# Control.net
KiCad netlist of a schematic drawn in Altium Designer
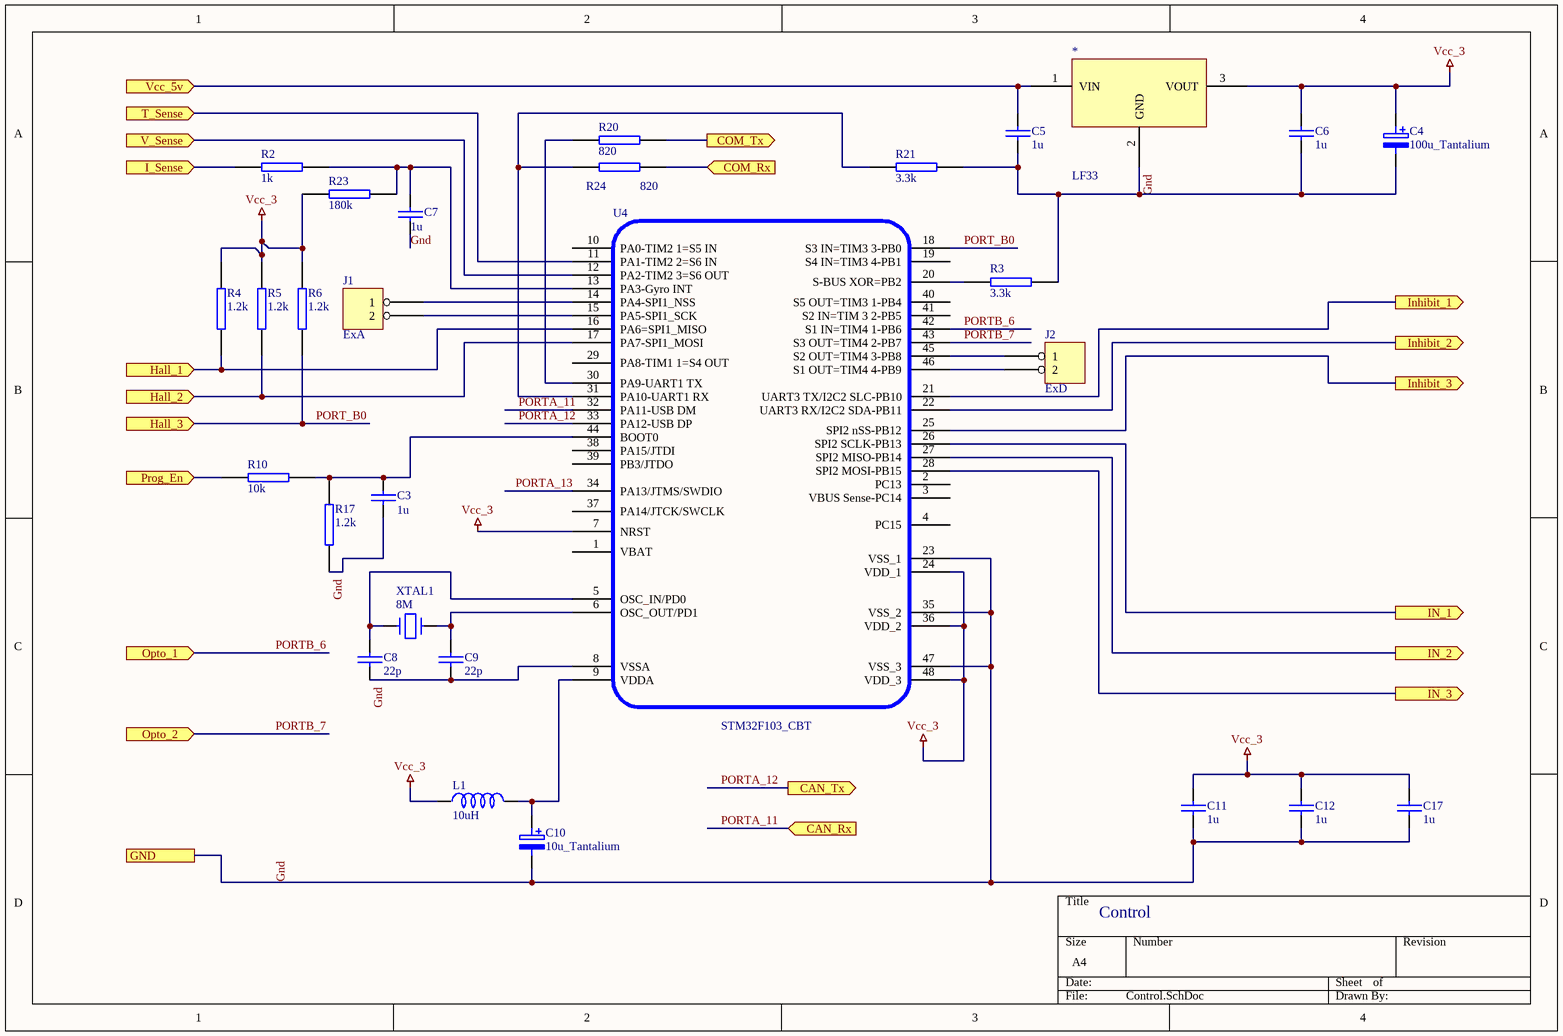
[diagram p0: Control.SchDoc]

(export (version "E")
  (design (tool "Eeschema 10.0.6"))
  (components
    (comp (ref "*") (value "LF33") (footprint "Dpak") (libsource (lib "CustomLib_Ver01") (part "LF33")))
    (comp (ref "C3")
      (value "1u")
      (footprint "1206_SMD")
      (description "Capacitor")
      (libsource (lib "Sch_Lib_24") (part "CAP"))
    )
    (comp (ref "C4")
      (value "100u_Tantalium")
      (footprint "Tantalum_9545")
      (libsource (lib "Sch_Lib_24") (part "CAP_ELECTRO"))
    )
    (comp (ref "C5")
      (value "1u")
      (footprint "1206_SMD")
      (description "Capacitor")
      (libsource (lib "Sch_Lib_24") (part "CAP"))
    )
    (comp (ref "C6")
      (value "1u")
      (footprint "1206_SMD")
      (description "Capacitor")
      (libsource (lib "Sch_Lib_24") (part "CAP"))
    )
    (comp (ref "C7")
      (value "1u")
      (footprint "1206_SMD")
      (description "Capacitor")
      (libsource (lib "Sch_Lib_24") (part "CAP"))
    )
    (comp (ref "C8")
      (value "22p")
      (footprint "0805")
      (description "Capacitor")
      (libsource (lib "Sch_Lib_24") (part "CAP"))
    )
    (comp (ref "C9")
      (value "22p")
      (footprint "0805")
      (description "Capacitor")
      (libsource (lib "Sch_Lib_24") (part "CAP"))
    )
    (comp (ref "C10")
      (value "10u_Tantalium")
      (footprint "Tantalum_9545")
      (libsource (lib "Sch_Lib_24") (part "CAP_ELECTRO"))
    )
    (comp (ref "C11")
      (value "1u")
      (footprint "1206_SMD")
      (description "Capacitor")
      (libsource (lib "Sch_Lib_24") (part "CAP"))
    )
    (comp (ref "C12")
      (value "1u")
      (footprint "1206_SMD")
      (description "Capacitor")
      (libsource (lib "Sch_Lib_24") (part "CAP"))
    )
    (comp (ref "C17")
      (value "1u")
      (footprint "1206_SMD")
      (description "Capacitor")
      (libsource (lib "Sch_Lib_24") (part "CAP"))
    )
    (comp (ref "J1") (value "ExA") (footprint "MHDR1X2") (libsource (lib "Sch_Lib_24") (part "HEADER 2")))
    (comp (ref "J2") (value "ExD") (footprint "MHDR1X2") (libsource (lib "") (part "HEADER 2_1")))
    (comp (ref "L1") (value "10uH") (footprint "1206_SMD") (libsource (lib "Sch_Lib_24") (part "INDUCTOR")))
    (comp (ref "R2") (value "1k") (footprint "0805") (libsource (lib "Sch_Lib_24") (part "RES2")))
    (comp (ref "R3") (value "3.3k") (footprint "0805") (libsource (lib "Sch_Lib_24") (part "RES2")))
    (comp (ref "R4") (value "1.2k") (footprint "1206_SMD") (libsource (lib "Sch_Lib_24") (part "RES2")))
    (comp (ref "R5") (value "1.2k") (footprint "1206_SMD") (libsource (lib "Sch_Lib_24") (part "RES2")))
    (comp (ref "R6") (value "1.2k") (footprint "1206_SMD") (libsource (lib "Sch_Lib_24") (part "RES2")))
    (comp (ref "R10") (value "10k") (footprint "0805") (libsource (lib "Sch_Lib_24") (part "RES2")))
    (comp (ref "R17") (value "1.2k") (footprint "0805") (libsource (lib "Sch_Lib_24") (part "RES2")))
    (comp (ref "R20") (value "820") (footprint "0805") (libsource (lib "Sch_Lib_24") (part "RES2")))
    (comp (ref "R21") (value "3.3k") (footprint "0805") (libsource (lib "Sch_Lib_24") (part "RES2")))
    (comp (ref "R23") (value "180k") (footprint "0805") (libsource (lib "Sch_Lib_24") (part "RES2")))
    (comp (ref "R24") (value "820") (footprint "0805") (libsource (lib "Sch_Lib_24") (part "RES2")))
    (comp (ref "U4")
      (value "STM32F103_CBT")
      (footprint "LQFP48")
      (description "ST Microcontroller")
      (libsource (lib "Sch_Lib_24") (part "STM32F103_CBT"))
    )
    (comp (ref "XTAL1")
      (value "8M")
      (footprint "xtal")
      (description "Crystal")
      (libsource (lib "Sch_Lib_24") (part "CRYSTAL"))
    )
  )
  (nets
    (net (code "1") (name "/COM_Rx") (class "Default")
      (node (ref "R24") (pin "1") (pinfunction "1_1") (pintype "passive"))
    )
    (net (code "2") (name "/COM_Tx") (class "Default")
      (node (ref "R20") (pin "1") (pinfunction "1_1") (pintype "passive"))
    )
    (net (code "3") (name "/Gnd") (class "Default")
      (node (ref "*") (pin "2") (pinfunction "GND_2") (pintype "passive"))
      (node (ref "C10") (pin "2") (pintype "passive"))
      (node (ref "C11") (pin "2") (pinfunction "2_2") (pintype "passive"))
      (node (ref "C12") (pin "2") (pinfunction "2_2") (pintype "passive"))
      (node (ref "C17") (pin "2") (pinfunction "2_2") (pintype "passive"))
      (node (ref "C3") (pin "2") (pinfunction "2_2") (pintype "passive"))
      (node (ref "C4") (pin "2") (pintype "passive"))
      (node (ref "C5") (pin "2") (pinfunction "2_2") (pintype "passive"))
      (node (ref "C6") (pin "2") (pinfunction "2_2") (pintype "passive"))
      (node (ref "C7") (pin "2") (pinfunction "2_2") (pintype "passive"))
      (node (ref "C8") (pin "2") (pinfunction "2_2") (pintype "passive"))
      (node (ref "C9") (pin "2") (pinfunction "2_2") (pintype "passive"))
      (node (ref "R17") (pin "1") (pinfunction "1_1") (pintype "passive"))
      (node (ref "R21") (pin "1") (pinfunction "1_1") (pintype "passive"))
      (node (ref "R3") (pin "1") (pinfunction "1_1") (pintype "passive"))
      (node (ref "U4") (pin "23") (pinfunction "VSS_1_23") (pintype "passive"))
      (node (ref "U4") (pin "35") (pinfunction "VSS_2_35") (pintype "passive"))
      (node (ref "U4") (pin "47") (pinfunction "VSS_3_47") (pintype "passive"))
      (node (ref "U4") (pin "8") (pinfunction "VSSA_8") (pintype "passive"))
    )
    (net (code "4") (name "/Hall_1") (class "Default")
      (node (ref "R4") (pin "1") (pinfunction "1_1") (pintype "passive"))
      (node (ref "U4") (pin "16") (pinfunction "PA6=SPI1_MISO_16") (pintype "passive"))
    )
    (net (code "5") (name "/Hall_2") (class "Default")
      (node (ref "R5") (pin "1") (pinfunction "1_1") (pintype "passive"))
      (node (ref "U4") (pin "17") (pinfunction "PA7-SPI1_MOSI_17") (pintype "passive"))
    )
    (net (code "6") (name "/IN_1") (class "Default")
      (node (ref "U4") (pin "26") (pinfunction "SPI2_SCLK-PB13_26") (pintype "passive"))
    )
    (net (code "7") (name "/IN_2") (class "Default")
      (node (ref "U4") (pin "27") (pinfunction "SPI2_MISO-PB14_27") (pintype "passive"))
    )
    (net (code "8") (name "/IN_3") (class "Default")
      (node (ref "U4") (pin "28") (pinfunction "SPI2_MOSI-PB15_28") (pintype "passive"))
    )
    (net (code "9") (name "/I_Sense") (class "Default")
      (node (ref "R2") (pin "1") (pinfunction "1_1") (pintype "passive"))
    )
    (net (code "10") (name "/Inhibit_1") (class "Default")
      (node (ref "U4") (pin "21") (pinfunction "UART3_TX/I2C2_SLC-PB10_21") (pintype "passive"))
    )
    (net (code "11") (name "/Inhibit_2") (class "Default")
      (node (ref "U4") (pin "22") (pinfunction "UART3_RX/I2C2_SDA-PB11_22") (pintype "passive"))
    )
    (net (code "12") (name "/Inhibit_3") (class "Default")
      (node (ref "U4") (pin "25") (pinfunction "SPI2_nSS-PB12_25") (pintype "passive"))
    )
    (net (code "13") (name "/PORTA_11") (class "Default")
      (node (ref "U4") (pin "32") (pinfunction "PA11-USB_DM_32") (pintype "passive"))
    )
    (net (code "14") (name "/PORTA_12") (class "Default")
      (node (ref "U4") (pin "33") (pinfunction "PA12-USB_DP_33") (pintype "passive"))
    )
    (net (code "15") (name "/PORTA_13") (class "Default")
      (node (ref "U4") (pin "34") (pinfunction "PA13/JTMS/SWDIO_34") (pintype "passive"))
    )
    (net (code "16") (name "/PORTB_6") (class "Default")
      (node (ref "U4") (pin "42") (pinfunction "S1_IN=TIM4_1-PB6_42") (pintype "passive"))
    )
    (net (code "17") (name "/PORTB_7") (class "Default")
      (node (ref "U4") (pin "43") (pinfunction "S3_OUT=TIM4_2-PB7_43") (pintype "passive"))
    )
    (net (code "18") (name "/PORT_B0") (class "Default")
      (node (ref "R6") (pin "1") (pinfunction "1_1") (pintype "passive"))
      (node (ref "U4") (pin "18") (pinfunction "S3_IN=TIM3_3-PB0_18") (pintype "passive"))
    )
    (net (code "19") (name "/Prog_En") (class "Default")
      (node (ref "R10") (pin "2") (pinfunction "2_2") (pintype "passive"))
    )
    (net (code "20") (name "/T_Sense") (class "Default")
      (node (ref "U4") (pin "11") (pinfunction "PA1-TIM2_2=S6_IN_11") (pintype "passive"))
    )
    (net (code "21") (name "/V_Sense") (class "Default")
      (node (ref "U4") (pin "12") (pinfunction "PA2-TIM2_3=S6_OUT_12") (pintype "passive"))
    )
    (net (code "22") (name "/Vcc_5v") (class "Default")
      (node (ref "*") (pin "1") (pinfunction "VIN_1") (pintype "passive"))
      (node (ref "C5") (pin "1") (pinfunction "1_1") (pintype "passive"))
    )
    (net (code "23") (name "Net-(U4-BOOT0)") (class "Default")
      (node (ref "C3") (pin "1") (pinfunction "1_1") (pintype "passive"))
      (node (ref "R10") (pin "1") (pinfunction "1_1") (pintype "passive"))
      (node (ref "R17") (pin "2") (pinfunction "2_2") (pintype "passive"))
      (node (ref "U4") (pin "44") (pinfunction "BOOT0_44") (pintype "passive"))
    )
    (net (code "24") (name "Net-(U4-OSC_IN{slash}PD0)") (class "Default")
      (node (ref "C8") (pin "1") (pinfunction "1_1") (pintype "passive"))
      (node (ref "U4") (pin "5") (pinfunction "OSC_IN/PD0_5") (pintype "passive"))
      (node (ref "XTAL1") (pin "1") (pinfunction "1_1") (pintype "passive"))
    )
    (net (code "25") (name "Net-(U4-OSC_OUT{slash}PD1)") (class "Default")
      (node (ref "C9") (pin "1") (pinfunction "1_1") (pintype "passive"))
      (node (ref "U4") (pin "6") (pinfunction "OSC_OUT/PD1_6") (pintype "passive"))
      (node (ref "XTAL1") (pin "2") (pinfunction "2_2") (pintype "passive"))
    )
    (net (code "26") (name "Net-(U4-PA3-Gyro_INT)") (class "Default")
      (node (ref "C7") (pin "1") (pinfunction "1_1") (pintype "passive"))
      (node (ref "R2") (pin "2") (pinfunction "2_2") (pintype "passive"))
      (node (ref "R23") (pin "1") (pinfunction "1_1") (pintype "passive"))
      (node (ref "U4") (pin "13") (pinfunction "PA3-Gyro_INT_13") (pintype "passive"))
    )
    (net (code "27") (name "Net-(U4-PA4-SPI1_NSS)") (class "Default")
      (node (ref "J1") (pin "1") (pinfunction "1_1") (pintype "passive"))
      (node (ref "U4") (pin "14") (pinfunction "PA4-SPI1_NSS_14") (pintype "passive"))
    )
    (net (code "28") (name "Net-(U4-PA5-SPI1_SCK)") (class "Default")
      (node (ref "J1") (pin "2") (pinfunction "2_2") (pintype "passive"))
      (node (ref "U4") (pin "15") (pinfunction "PA5-SPI1_SCK_15") (pintype "passive"))
    )
    (net (code "29") (name "Net-(U4-PA9-UART1_TX)") (class "Default")
      (node (ref "R20") (pin "2") (pinfunction "2_2") (pintype "passive"))
      (node (ref "U4") (pin "30") (pinfunction "PA9-UART1_TX_30") (pintype "passive"))
    )
    (net (code "30") (name "Net-(U4-PA10-UART1_RX)") (class "Default")
      (node (ref "R21") (pin "2") (pinfunction "2_2") (pintype "passive"))
      (node (ref "R24") (pin "2") (pinfunction "2_2") (pintype "passive"))
      (node (ref "U4") (pin "31") (pinfunction "PA10-UART1_RX_31") (pintype "passive"))
    )
    (net (code "31") (name "Net-(U4-S-BUS_XOR=PB2)") (class "Default")
      (node (ref "R3") (pin "2") (pinfunction "2_2") (pintype "passive"))
      (node (ref "U4") (pin "20") (pinfunction "S-BUS_XOR=PB2_20") (pintype "passive"))
    )
    (net (code "32") (name "Net-(U4-S1_OUT=TIM4_4-PB9)") (class "Default")
      (node (ref "J2") (pin "2") (pinfunction "2_2") (pintype "passive"))
      (node (ref "U4") (pin "46") (pinfunction "S1_OUT=TIM4_4-PB9_46") (pintype "passive"))
    )
    (net (code "33") (name "Net-(U4-S2_OUT=TIM4_3-PB8)") (class "Default")
      (node (ref "J2") (pin "1") (pinfunction "1_1") (pintype "passive"))
      (node (ref "U4") (pin "45") (pinfunction "S2_OUT=TIM4_3-PB8_45") (pintype "passive"))
    )
    (net (code "34") (name "Net-(U4-VDDA)") (class "Default")
      (node (ref "C10") (pin "1") (pintype "passive"))
      (node (ref "L1") (pin "2") (pintype "passive"))
      (node (ref "U4") (pin "9") (pinfunction "VDDA_9") (pintype "passive"))
    )
    (net (code "35") (name "Vcc_3") (class "Default")
      (node (ref "*") (pin "3") (pinfunction "VOUT_3") (pintype "passive"))
      (node (ref "C11") (pin "1") (pinfunction "1_1") (pintype "passive"))
      (node (ref "C12") (pin "1") (pinfunction "1_1") (pintype "passive"))
      (node (ref "C17") (pin "1") (pinfunction "1_1") (pintype "passive"))
      (node (ref "C4") (pin "1") (pintype "passive"))
      (node (ref "C6") (pin "1") (pinfunction "1_1") (pintype "passive"))
      (node (ref "L1") (pin "1") (pintype "passive"))
      (node (ref "R23") (pin "2") (pinfunction "2_2") (pintype "passive"))
      (node (ref "R4") (pin "2") (pinfunction "2_2") (pintype "passive"))
      (node (ref "R5") (pin "2") (pinfunction "2_2") (pintype "passive"))
      (node (ref "R6") (pin "2") (pinfunction "2_2") (pintype "passive"))
      (node (ref "U4") (pin "24") (pinfunction "VDD_1_24") (pintype "passive"))
      (node (ref "U4") (pin "36") (pinfunction "VDD_2_36") (pintype "passive"))
      (node (ref "U4") (pin "48") (pinfunction "VDD_3_48") (pintype "passive"))
      (node (ref "U4") (pin "7") (pinfunction "NRST_7") (pintype "passive"))
    )
    (net (code "36") (name "unconnected-(U4-PA0-TIM2_1=S5_IN-Pad10)") (class "Default")
      (node (ref "U4") (pin "10") (pinfunction "PA0-TIM2_1=S5_IN_10") (pintype "passive"))
    )
    (net (code "37") (name "unconnected-(U4-PA8-TIM1_1=S4_OUT-Pad29)") (class "Default")
      (node (ref "U4") (pin "29") (pinfunction "PA8-TIM1_1=S4_OUT_29") (pintype "passive"))
    )
    (net (code "38") (name "unconnected-(U4-PA14{slash}JTCK{slash}SWCLK-Pad37)") (class "Default")
      (node (ref "U4") (pin "37") (pinfunction "PA14/JTCK/SWCLK_37") (pintype "passive"))
    )
    (net (code "39") (name "unconnected-(U4-PA15{slash}JTDI-Pad38)") (class "Default")
      (node (ref "U4") (pin "38") (pinfunction "PA15/JTDI_38") (pintype "passive"))
    )
    (net (code "40") (name "unconnected-(U4-PB3{slash}JTDO-Pad39)") (class "Default")
      (node (ref "U4") (pin "39") (pinfunction "PB3/JTDO_39") (pintype "passive"))
    )
    (net (code "41") (name "unconnected-(U4-PC13-Pad2)") (class "Default")
      (node (ref "U4") (pin "2") (pinfunction "PC13_2") (pintype "passive"))
    )
    (net (code "42") (name "unconnected-(U4-PC15-Pad4)") (class "Default")
      (node (ref "U4") (pin "4") (pinfunction "PC15_4") (pintype "passive"))
    )
    (net (code "43") (name "unconnected-(U4-S2_IN=TIM_3_2-PB5-Pad41)") (class "Default")
      (node (ref "U4") (pin "41") (pinfunction "S2_IN=TIM_3_2-PB5_41") (pintype "passive"))
    )
    (net (code "44") (name "unconnected-(U4-S4_IN=TIM3_4-PB1-Pad19)") (class "Default")
      (node (ref "U4") (pin "19") (pinfunction "S4_IN=TIM3_4-PB1_19") (pintype "passive"))
    )
    (net (code "45") (name "unconnected-(U4-S5_OUT=TIM3_1-PB4-Pad40)") (class "Default")
      (node (ref "U4") (pin "40") (pinfunction "S5_OUT=TIM3_1-PB4_40") (pintype "passive"))
    )
    (net (code "46") (name "unconnected-(U4-VBAT-Pad1)") (class "Default")
      (node (ref "U4") (pin "1") (pinfunction "VBAT_1") (pintype "passive"))
    )
    (net (code "47") (name "unconnected-(U4-VBUS_Sense-PC14-Pad3)") (class "Default")
      (node (ref "U4") (pin "3") (pinfunction "VBUS_Sense-PC14_3") (pintype "passive"))
    )
  )
)
